# pro-cap.net
KiCad netlist of a schematic drawn in EAGLE
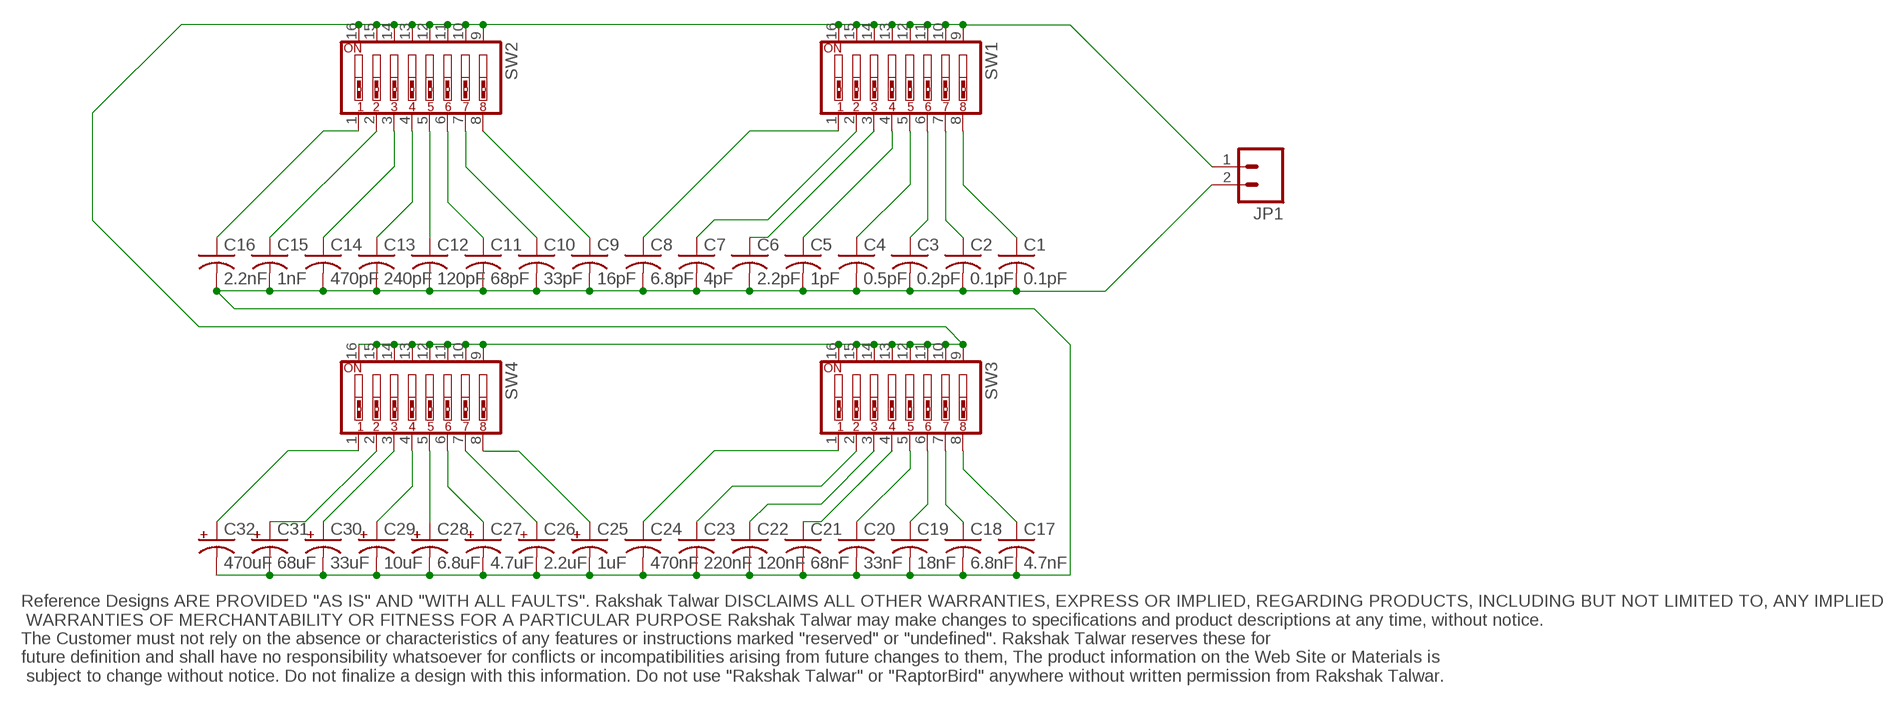
[diagram p0: schematic, sheet 1]

(export (version "E")
  (design (tool "Eeschema 10.0.6"))
  (components
    (comp (ref "C1")
      (value "0.1pF")
      (footprint "eagle-import:C0603")
      (libsource (lib "eagle-import") (part "C-USC0603"))
    )
    (comp (ref "C2")
      (value "0.1pF")
      (footprint "eagle-import:C0603")
      (libsource (lib "eagle-import") (part "C-USC0603"))
    )
    (comp (ref "C3")
      (value "0.2pF")
      (footprint "eagle-import:C0805")
      (libsource (lib "eagle-import") (part "C-USC0805"))
    )
    (comp (ref "C4")
      (value "0.5pF")
      (footprint "eagle-import:C0603")
      (libsource (lib "eagle-import") (part "C-USC0603"))
    )
    (comp (ref "C5")
      (value "1pF")
      (footprint "eagle-import:C0805")
      (libsource (lib "eagle-import") (part "C-USC0805"))
    )
    (comp (ref "C6")
      (value "2.2pF")
      (footprint "eagle-import:C1206")
      (libsource (lib "eagle-import") (part "C-USC1206"))
    )
    (comp (ref "C7")
      (value "4pF")
      (footprint "eagle-import:C0603")
      (libsource (lib "eagle-import") (part "C-USC0603"))
    )
    (comp (ref "C8")
      (value "6.8pF")
      (footprint "eagle-import:C0805")
      (libsource (lib "eagle-import") (part "C-USC0805"))
    )
    (comp (ref "C9")
      (value "16pF")
      (footprint "eagle-import:C0603")
      (libsource (lib "eagle-import") (part "C-USC0603"))
    )
    (comp (ref "C10")
      (value "33pF")
      (footprint "eagle-import:C0603")
      (libsource (lib "eagle-import") (part "C-USC0603"))
    )
    (comp (ref "C11")
      (value "68pF")
      (footprint "eagle-import:C0603")
      (libsource (lib "eagle-import") (part "C-USC0603"))
    )
    (comp (ref "C12")
      (value "120pF")
      (footprint "eagle-import:C0805")
      (libsource (lib "eagle-import") (part "C-USC0805"))
    )
    (comp (ref "C13")
      (value "240pF")
      (footprint "eagle-import:C0603")
      (libsource (lib "eagle-import") (part "C-USC0603"))
    )
    (comp (ref "C14")
      (value "470pF")
      (footprint "eagle-import:C0805")
      (libsource (lib "eagle-import") (part "C-USC0805"))
    )
    (comp (ref "C15")
      (value "1nF")
      (footprint "eagle-import:C0603")
      (libsource (lib "eagle-import") (part "C-USC0603"))
    )
    (comp (ref "C16")
      (value "2.2nF")
      (footprint "eagle-import:C0603")
      (libsource (lib "eagle-import") (part "C-USC0603"))
    )
    (comp (ref "C17")
      (value "4.7nF")
      (footprint "eagle-import:C0603")
      (libsource (lib "eagle-import") (part "C-USC0603"))
    )
    (comp (ref "C18")
      (value "6.8nF")
      (footprint "eagle-import:C0805")
      (libsource (lib "eagle-import") (part "C-USC0805"))
    )
    (comp (ref "C19")
      (value "18nF")
      (footprint "eagle-import:C0603")
      (libsource (lib "eagle-import") (part "C-USC0603"))
    )
    (comp (ref "C20")
      (value "33nF")
      (footprint "eagle-import:C0805")
      (libsource (lib "eagle-import") (part "C-USC0805"))
    )
    (comp (ref "C21")
      (value "68nF")
      (footprint "eagle-import:C0603")
      (libsource (lib "eagle-import") (part "C-USC0603"))
    )
    (comp (ref "C22")
      (value "120nF")
      (footprint "eagle-import:C0603")
      (libsource (lib "eagle-import") (part "C-USC0603"))
    )
    (comp (ref "C23")
      (value "220nF")
      (footprint "eagle-import:C0603")
      (libsource (lib "eagle-import") (part "C-USC0603"))
    )
    (comp (ref "C24")
      (value "470nF")
      (footprint "eagle-import:C0603")
      (libsource (lib "eagle-import") (part "C-USC0603"))
    )
    (comp (ref "C25")
      (value "1uF")
      (footprint "eagle-import:PANASONIC_B")
      (libsource (lib "eagle-import") (part "CPOL-USB"))
    )
    (comp (ref "C26")
      (value "2.2uF")
      (footprint "eagle-import:PANASONIC_B")
      (libsource (lib "eagle-import") (part "CPOL-USB"))
    )
    (comp (ref "C27")
      (value "4.7uF")
      (footprint "eagle-import:PANASONIC_B")
      (libsource (lib "eagle-import") (part "CPOL-USB"))
    )
    (comp (ref "C28")
      (value "6.8uF")
      (footprint "eagle-import:E1,8-4")
      (libsource (lib "eagle-import") (part "rcl_CPOL-USE1.8-4"))
    )
    (comp (ref "C29")
      (value "10uF")
      (footprint "eagle-import:E2-5")
      (libsource (lib "eagle-import") (part "rcl_CPOL-USE2-5"))
    )
    (comp (ref "C30")
      (value "33uF")
      (footprint "eagle-import:E2-5")
      (libsource (lib "eagle-import") (part "rcl_CPOL-USE2-5"))
    )
    (comp (ref "C31")
      (value "68uF")
      (footprint "eagle-import:E2,5-6")
      (libsource (lib "eagle-import") (part "rcl_CPOL-USE2.5-6"))
    )
    (comp (ref "C32")
      (value "470uF")
      (footprint "eagle-import:E5-10,5")
      (libsource (lib "eagle-import") (part "rcl_CPOL-USE5-10.5"))
    )
    (comp (ref "JP1")
      (value "M023.5MM")
      (footprint "eagle-import:SCREWTERMINAL-3.5MM-2")
      (libsource (lib "eagle-import") (part "M023.5MM"))
    )
    (comp (ref "SW1")
      (value "SW_DIP-8")
      (footprint "eagle-import:EDG-08")
      (libsource (lib "eagle-import") (part "SW_DIP-8"))
    )
    (comp (ref "SW2")
      (value "SW_DIP-8")
      (footprint "eagle-import:EDG-08")
      (libsource (lib "eagle-import") (part "SW_DIP-8"))
    )
    (comp (ref "SW3")
      (value "SW_DIP-8")
      (footprint "eagle-import:EDG-08")
      (libsource (lib "eagle-import") (part "SW_DIP-8"))
    )
    (comp (ref "SW4")
      (value "SW_DIP-8")
      (footprint "eagle-import:EDG-08")
      (libsource (lib "eagle-import") (part "SW_DIP-8"))
    )
  )
  (nets
    (net (code "1") (name "Net-(C1-Pad1)") (class "Default")
      (node (ref "C1") (pin "1") (pinfunction "1_1") (pintype "passive"))
      (node (ref "SW1") (pin "8") (pinfunction "8_8") (pintype "passive"))
    )
    (net (code "2") (name "Net-(C1-Pad2)") (class "Default")
      (node (ref "C1") (pin "2") (pinfunction "2_2") (pintype "passive"))
      (node (ref "C10") (pin "2") (pinfunction "2_2") (pintype "passive"))
      (node (ref "C11") (pin "2") (pinfunction "2_2") (pintype "passive"))
      (node (ref "C12") (pin "2") (pinfunction "2_2") (pintype "passive"))
      (node (ref "C13") (pin "2") (pinfunction "2_2") (pintype "passive"))
      (node (ref "C14") (pin "2") (pinfunction "2_2") (pintype "passive"))
      (node (ref "C15") (pin "2") (pinfunction "2_2") (pintype "passive"))
      (node (ref "C16") (pin "2") (pinfunction "2_2") (pintype "passive"))
      (node (ref "C17") (pin "2") (pinfunction "2_2") (pintype "passive"))
      (node (ref "C18") (pin "2") (pinfunction "2_2") (pintype "passive"))
      (node (ref "C19") (pin "2") (pinfunction "2_2") (pintype "passive"))
      (node (ref "C2") (pin "2") (pinfunction "2_2") (pintype "passive"))
      (node (ref "C20") (pin "2") (pinfunction "2_2") (pintype "passive"))
      (node (ref "C21") (pin "2") (pinfunction "2_2") (pintype "passive"))
      (node (ref "C22") (pin "2") (pinfunction "2_2") (pintype "passive"))
      (node (ref "C23") (pin "2") (pinfunction "2_2") (pintype "passive"))
      (node (ref "C24") (pin "2") (pinfunction "2_2") (pintype "passive"))
      (node (ref "C25") (pin "-") (pinfunction "-_-") (pintype "passive"))
      (node (ref "C26") (pin "-") (pinfunction "-_-") (pintype "passive"))
      (node (ref "C27") (pin "-") (pinfunction "-_-") (pintype "passive"))
      (node (ref "C28") (pin "-") (pinfunction "-_-") (pintype "passive"))
      (node (ref "C29") (pin "-") (pinfunction "-_-") (pintype "passive"))
      (node (ref "C3") (pin "2") (pinfunction "2_2") (pintype "passive"))
      (node (ref "C30") (pin "-") (pinfunction "-_-") (pintype "passive"))
      (node (ref "C31") (pin "-") (pinfunction "-_-") (pintype "passive"))
      (node (ref "C32") (pin "-") (pinfunction "-_-") (pintype "passive"))
      (node (ref "C4") (pin "2") (pinfunction "2_2") (pintype "passive"))
      (node (ref "C5") (pin "2") (pinfunction "2_2") (pintype "passive"))
      (node (ref "C6") (pin "2") (pinfunction "2_2") (pintype "passive"))
      (node (ref "C7") (pin "2") (pinfunction "2_2") (pintype "passive"))
      (node (ref "C8") (pin "2") (pinfunction "2_2") (pintype "passive"))
      (node (ref "C9") (pin "2") (pinfunction "2_2") (pintype "passive"))
      (node (ref "JP1") (pin "2") (pinfunction "2_2") (pintype "passive"))
    )
    (net (code "3") (name "Net-(C2-Pad1)") (class "Default")
      (node (ref "C2") (pin "1") (pinfunction "1_1") (pintype "passive"))
      (node (ref "SW1") (pin "7") (pinfunction "7_7") (pintype "passive"))
    )
    (net (code "4") (name "Net-(C3-Pad1)") (class "Default")
      (node (ref "C3") (pin "1") (pinfunction "1_1") (pintype "passive"))
      (node (ref "SW1") (pin "6") (pinfunction "6_6") (pintype "passive"))
    )
    (net (code "5") (name "Net-(C4-Pad1)") (class "Default")
      (node (ref "C4") (pin "1") (pinfunction "1_1") (pintype "passive"))
      (node (ref "SW1") (pin "5") (pinfunction "5_5") (pintype "passive"))
    )
    (net (code "6") (name "Net-(C5-Pad1)") (class "Default")
      (node (ref "C5") (pin "1") (pinfunction "1_1") (pintype "passive"))
      (node (ref "SW1") (pin "4") (pinfunction "4_4") (pintype "passive"))
    )
    (net (code "7") (name "Net-(C6-Pad1)") (class "Default")
      (node (ref "C6") (pin "1") (pinfunction "1_1") (pintype "passive"))
      (node (ref "SW1") (pin "3") (pinfunction "3_3") (pintype "passive"))
    )
    (net (code "8") (name "Net-(C7-Pad1)") (class "Default")
      (node (ref "C7") (pin "1") (pinfunction "1_1") (pintype "passive"))
      (node (ref "SW1") (pin "2") (pinfunction "2_2") (pintype "passive"))
    )
    (net (code "9") (name "Net-(C8-Pad1)") (class "Default")
      (node (ref "C8") (pin "1") (pinfunction "1_1") (pintype "passive"))
      (node (ref "SW1") (pin "1") (pinfunction "1_1") (pintype "passive"))
    )
    (net (code "10") (name "Net-(C9-Pad1)") (class "Default")
      (node (ref "C9") (pin "1") (pinfunction "1_1") (pintype "passive"))
      (node (ref "SW2") (pin "8") (pinfunction "8_8") (pintype "passive"))
    )
    (net (code "11") (name "Net-(C10-Pad1)") (class "Default")
      (node (ref "C10") (pin "1") (pinfunction "1_1") (pintype "passive"))
      (node (ref "SW2") (pin "7") (pinfunction "7_7") (pintype "passive"))
    )
    (net (code "12") (name "Net-(C11-Pad1)") (class "Default")
      (node (ref "C11") (pin "1") (pinfunction "1_1") (pintype "passive"))
      (node (ref "SW2") (pin "6") (pinfunction "6_6") (pintype "passive"))
    )
    (net (code "13") (name "Net-(C12-Pad1)") (class "Default")
      (node (ref "C12") (pin "1") (pinfunction "1_1") (pintype "passive"))
      (node (ref "SW2") (pin "5") (pinfunction "5_5") (pintype "passive"))
    )
    (net (code "14") (name "Net-(C13-Pad1)") (class "Default")
      (node (ref "C13") (pin "1") (pinfunction "1_1") (pintype "passive"))
      (node (ref "SW2") (pin "4") (pinfunction "4_4") (pintype "passive"))
    )
    (net (code "15") (name "Net-(C14-Pad1)") (class "Default")
      (node (ref "C14") (pin "1") (pinfunction "1_1") (pintype "passive"))
      (node (ref "SW2") (pin "3") (pinfunction "3_3") (pintype "passive"))
    )
    (net (code "16") (name "Net-(C15-Pad1)") (class "Default")
      (node (ref "C15") (pin "1") (pinfunction "1_1") (pintype "passive"))
      (node (ref "SW2") (pin "2") (pinfunction "2_2") (pintype "passive"))
    )
    (net (code "17") (name "Net-(C16-Pad1)") (class "Default")
      (node (ref "C16") (pin "1") (pinfunction "1_1") (pintype "passive"))
      (node (ref "SW2") (pin "1") (pinfunction "1_1") (pintype "passive"))
    )
    (net (code "18") (name "Net-(C17-Pad1)") (class "Default")
      (node (ref "C17") (pin "1") (pinfunction "1_1") (pintype "passive"))
      (node (ref "SW3") (pin "8") (pinfunction "8_8") (pintype "passive"))
    )
    (net (code "19") (name "Net-(C18-Pad1)") (class "Default")
      (node (ref "C18") (pin "1") (pinfunction "1_1") (pintype "passive"))
      (node (ref "SW3") (pin "7") (pinfunction "7_7") (pintype "passive"))
    )
    (net (code "20") (name "Net-(C19-Pad1)") (class "Default")
      (node (ref "C19") (pin "1") (pinfunction "1_1") (pintype "passive"))
      (node (ref "SW3") (pin "6") (pinfunction "6_6") (pintype "passive"))
    )
    (net (code "21") (name "Net-(C20-Pad1)") (class "Default")
      (node (ref "C20") (pin "1") (pinfunction "1_1") (pintype "passive"))
      (node (ref "SW3") (pin "5") (pinfunction "5_5") (pintype "passive"))
    )
    (net (code "22") (name "Net-(C21-Pad1)") (class "Default")
      (node (ref "C21") (pin "1") (pinfunction "1_1") (pintype "passive"))
      (node (ref "SW3") (pin "4") (pinfunction "4_4") (pintype "passive"))
    )
    (net (code "23") (name "Net-(C22-Pad1)") (class "Default")
      (node (ref "C22") (pin "1") (pinfunction "1_1") (pintype "passive"))
      (node (ref "SW3") (pin "3") (pinfunction "3_3") (pintype "passive"))
    )
    (net (code "24") (name "Net-(C23-Pad1)") (class "Default")
      (node (ref "C23") (pin "1") (pinfunction "1_1") (pintype "passive"))
      (node (ref "SW3") (pin "2") (pinfunction "2_2") (pintype "passive"))
    )
    (net (code "25") (name "Net-(C24-Pad1)") (class "Default")
      (node (ref "C24") (pin "1") (pinfunction "1_1") (pintype "passive"))
      (node (ref "SW3") (pin "1") (pinfunction "1_1") (pintype "passive"))
    )
    (net (code "26") (name "Net-(C25-Pad+)") (class "Default")
      (node (ref "C25") (pin "+") (pinfunction "+_+") (pintype "passive"))
      (node (ref "SW4") (pin "8") (pinfunction "8_8") (pintype "passive"))
    )
    (net (code "27") (name "Net-(C26-Pad+)") (class "Default")
      (node (ref "C26") (pin "+") (pinfunction "+_+") (pintype "passive"))
      (node (ref "SW4") (pin "7") (pinfunction "7_7") (pintype "passive"))
    )
    (net (code "28") (name "Net-(C27-Pad+)") (class "Default")
      (node (ref "C27") (pin "+") (pinfunction "+_+") (pintype "passive"))
      (node (ref "SW4") (pin "6") (pinfunction "6_6") (pintype "passive"))
    )
    (net (code "29") (name "Net-(C28-Pad+)") (class "Default")
      (node (ref "C28") (pin "+") (pinfunction "+_+") (pintype "passive"))
      (node (ref "SW4") (pin "5") (pinfunction "5_5") (pintype "passive"))
    )
    (net (code "30") (name "Net-(C29-Pad+)") (class "Default")
      (node (ref "C29") (pin "+") (pinfunction "+_+") (pintype "passive"))
      (node (ref "SW4") (pin "4") (pinfunction "4_4") (pintype "passive"))
    )
    (net (code "31") (name "Net-(C30-Pad+)") (class "Default")
      (node (ref "C30") (pin "+") (pinfunction "+_+") (pintype "passive"))
      (node (ref "SW4") (pin "3") (pinfunction "3_3") (pintype "passive"))
    )
    (net (code "32") (name "Net-(C31-Pad+)") (class "Default")
      (node (ref "C31") (pin "+") (pinfunction "+_+") (pintype "passive"))
      (node (ref "SW4") (pin "2") (pinfunction "2_2") (pintype "passive"))
    )
    (net (code "33") (name "Net-(C32-Pad+)") (class "Default")
      (node (ref "C32") (pin "+") (pinfunction "+_+") (pintype "passive"))
      (node (ref "SW4") (pin "1") (pinfunction "1_1") (pintype "passive"))
    )
    (net (code "34") (name "Net-(JP1-Pad1)") (class "Default")
      (node (ref "JP1") (pin "1") (pinfunction "1_1") (pintype "passive"))
      (node (ref "SW1") (pin "10") (pinfunction "10_10") (pintype "passive"))
      (node (ref "SW1") (pin "11") (pinfunction "11_11") (pintype "passive"))
      (node (ref "SW1") (pin "12") (pinfunction "12_12") (pintype "passive"))
      (node (ref "SW1") (pin "13") (pinfunction "13_13") (pintype "passive"))
      (node (ref "SW1") (pin "14") (pinfunction "14_14") (pintype "passive"))
      (node (ref "SW1") (pin "15") (pinfunction "15_15") (pintype "passive"))
      (node (ref "SW1") (pin "16") (pinfunction "16_16") (pintype "passive"))
      (node (ref "SW1") (pin "9") (pinfunction "9_9") (pintype "passive"))
      (node (ref "SW2") (pin "10") (pinfunction "10_10") (pintype "passive"))
      (node (ref "SW2") (pin "11") (pinfunction "11_11") (pintype "passive"))
      (node (ref "SW2") (pin "12") (pinfunction "12_12") (pintype "passive"))
      (node (ref "SW2") (pin "13") (pinfunction "13_13") (pintype "passive"))
      (node (ref "SW2") (pin "14") (pinfunction "14_14") (pintype "passive"))
      (node (ref "SW2") (pin "15") (pinfunction "15_15") (pintype "passive"))
      (node (ref "SW2") (pin "16") (pinfunction "16_16") (pintype "passive"))
      (node (ref "SW2") (pin "9") (pinfunction "9_9") (pintype "passive"))
      (node (ref "SW3") (pin "10") (pinfunction "10_10") (pintype "passive"))
      (node (ref "SW3") (pin "11") (pinfunction "11_11") (pintype "passive"))
      (node (ref "SW3") (pin "12") (pinfunction "12_12") (pintype "passive"))
      (node (ref "SW3") (pin "13") (pinfunction "13_13") (pintype "passive"))
      (node (ref "SW3") (pin "14") (pinfunction "14_14") (pintype "passive"))
      (node (ref "SW3") (pin "15") (pinfunction "15_15") (pintype "passive"))
      (node (ref "SW3") (pin "16") (pinfunction "16_16") (pintype "passive"))
      (node (ref "SW3") (pin "9") (pinfunction "9_9") (pintype "passive"))
      (node (ref "SW4") (pin "10") (pinfunction "10_10") (pintype "passive"))
      (node (ref "SW4") (pin "11") (pinfunction "11_11") (pintype "passive"))
      (node (ref "SW4") (pin "12") (pinfunction "12_12") (pintype "passive"))
      (node (ref "SW4") (pin "13") (pinfunction "13_13") (pintype "passive"))
      (node (ref "SW4") (pin "14") (pinfunction "14_14") (pintype "passive"))
      (node (ref "SW4") (pin "15") (pinfunction "15_15") (pintype "passive"))
      (node (ref "SW4") (pin "16") (pinfunction "16_16") (pintype "passive"))
      (node (ref "SW4") (pin "9") (pinfunction "9_9") (pintype "passive"))
    )
  )
)
